# Level-Translator.net
KiCad netlist of a schematic drawn in Altium Designer
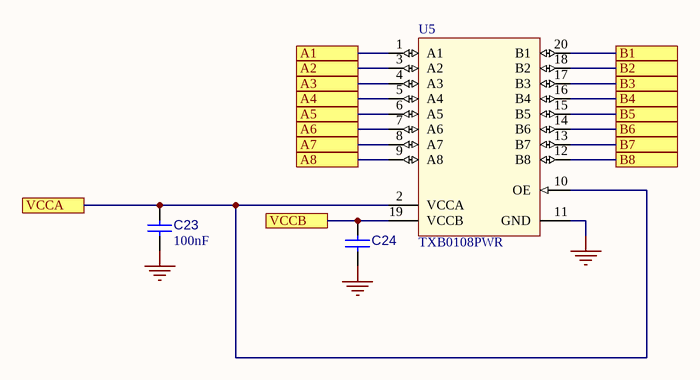
[diagram p0: Level-Translator.SchDoc]

(export (version "E")
  (design (tool "Eeschema 10.0.6"))
  (components
    (comp (ref "C23")
      (value "100nF")
      (footprint "C_1005[0402]")
      (description "Capacitor type 1")
      (fields (field (name "TOLERANCE") "10%") (field (name "Comment") "Cap 100nF 0402"))
      (libsource (lib "TEP_243-Altium_DBLib") (part "capacitor"))
    )
    (comp (ref "C24")
      (value "Cap 100nF 0402")
      (footprint "C_1005[0402]")
      (description "Capacitor type 1")
      (fields (field (name "TOLERANCE") "10%"))
      (libsource (lib "TEP_243-Altium_DBLib") (part "capacitor"))
    )
    (comp (ref "U5")
      (value "TXB0108PWR")
      (footprint "U_TSSOP65P660X450-20")
      (description "IC 8-Bit Bidirectional Voltage-Level Translator with Auto-Direction Sensing 20-Pin TSSOP (PW)")
      (libsource (lib "TEP_243-Altium_Library") (part "U_TXB0108PWR"))
    )
  )
  (nets
    (net (code "1") (name "/A1") (class "Default")
      (node (ref "U5") (pin "1") (pinfunction "A1_1") (pintype "bidirectional"))
    )
    (net (code "2") (name "/A2") (class "Default")
      (node (ref "U5") (pin "3") (pinfunction "A2_3") (pintype "bidirectional"))
    )
    (net (code "3") (name "/A3") (class "Default")
      (node (ref "U5") (pin "4") (pinfunction "A3_4") (pintype "bidirectional"))
    )
    (net (code "4") (name "/A4") (class "Default")
      (node (ref "U5") (pin "5") (pinfunction "A4_5") (pintype "bidirectional"))
    )
    (net (code "5") (name "/A5") (class "Default")
      (node (ref "U5") (pin "6") (pinfunction "A5_6") (pintype "bidirectional"))
    )
    (net (code "6") (name "/A6") (class "Default")
      (node (ref "U5") (pin "7") (pinfunction "A6_7") (pintype "bidirectional"))
    )
    (net (code "7") (name "/A7") (class "Default")
      (node (ref "U5") (pin "8") (pinfunction "A7_8") (pintype "bidirectional"))
    )
    (net (code "8") (name "/A8") (class "Default")
      (node (ref "U5") (pin "9") (pinfunction "A8_9") (pintype "bidirectional"))
    )
    (net (code "9") (name "/B1") (class "Default")
      (node (ref "U5") (pin "20") (pinfunction "B1_20") (pintype "bidirectional"))
    )
    (net (code "10") (name "/B2") (class "Default")
      (node (ref "U5") (pin "18") (pinfunction "B2_18") (pintype "bidirectional"))
    )
    (net (code "11") (name "/B3") (class "Default")
      (node (ref "U5") (pin "17") (pinfunction "B3_17") (pintype "bidirectional"))
    )
    (net (code "12") (name "/B4") (class "Default")
      (node (ref "U5") (pin "16") (pinfunction "B4_16") (pintype "bidirectional"))
    )
    (net (code "13") (name "/B5") (class "Default")
      (node (ref "U5") (pin "15") (pinfunction "B5_15") (pintype "bidirectional"))
    )
    (net (code "14") (name "/B6") (class "Default")
      (node (ref "U5") (pin "14") (pinfunction "B6_14") (pintype "bidirectional"))
    )
    (net (code "15") (name "/B7") (class "Default")
      (node (ref "U5") (pin "13") (pinfunction "B7_13") (pintype "bidirectional"))
    )
    (net (code "16") (name "/B8") (class "Default")
      (node (ref "U5") (pin "12") (pinfunction "B8_12") (pintype "bidirectional"))
    )
    (net (code "17") (name "/VCCA") (class "Default")
      (node (ref "C23") (pin "2") (pinfunction "2_2") (pintype "passive"))
      (node (ref "U5") (pin "10") (pinfunction "OE_10") (pintype "input"))
      (node (ref "U5") (pin "2") (pinfunction "VCCA_2") (pintype "power_in"))
    )
    (net (code "18") (name "/VCCB") (class "Default")
      (node (ref "C24") (pin "2") (pinfunction "2_2") (pintype "passive"))
      (node (ref "U5") (pin "19") (pinfunction "VCCB_19") (pintype "power_in"))
    )
    (net (code "19") (name "GND") (class "Default")
      (node (ref "C23") (pin "1") (pinfunction "1_1") (pintype "passive"))
      (node (ref "C24") (pin "1") (pinfunction "1_1") (pintype "passive"))
      (node (ref "U5") (pin "11") (pinfunction "GND_11") (pintype "power_in"))
    )
  )
)
